# Test_Schematic.net
KiCad netlist of a schematic drawn in Altium Designer
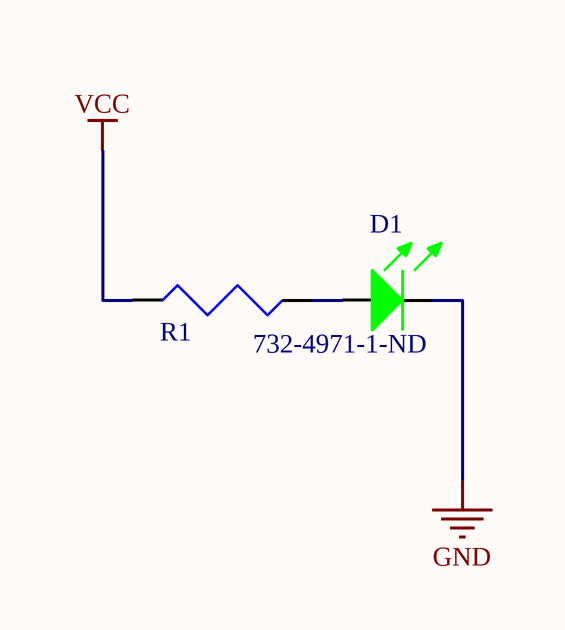
[diagram p0: Test Schematic.SchDoc]

(export (version "E")
  (design (tool "Eeschema 10.0.6"))
  (components
    (comp (ref "D1")
      (value "150060GS75000")
      (footprint "LED_Green_0603_3.2V")
      (description "LED Green Vf= 3.2V If = 0.025A\r\n150060GS75000")
      (fields (field (name "SUPPLIER PART NUMBER 1") "732-4971-1-ND"))
      (libsource (lib "UWRT") (part "LED_Green_0603_3.2V"))
    )
    (comp (ref "R1")
      (value "RK73B1JTTD101J")
      (footprint "PASSIIVE_RESISTOR_0603")
      (description "RES 100 OHM 5% 1/8W 0603")
      (libsource (lib "UWRT") (part "PASSIVE_RESISTOR_100_0603"))
    )
  )
  (nets
    (net (code "1") (name "GND") (class "Default")
      (node (ref "D1") (pin "2") (pinfunction "2_2") (pintype "passive"))
    )
    (net (code "2") (name "Net-(D1-Pad1)") (class "Default")
      (node (ref "D1") (pin "1") (pinfunction "1_1") (pintype "passive"))
      (node (ref "R1") (pin "1") (pinfunction "1_1") (pintype "passive"))
    )
    (net (code "3") (name "VCC") (class "Default")
      (node (ref "R1") (pin "2") (pinfunction "2_2") (pintype "passive"))
    )
  )
)
